# ADC_Circuit.net
KiCad netlist of a schematic drawn in Altium Designer
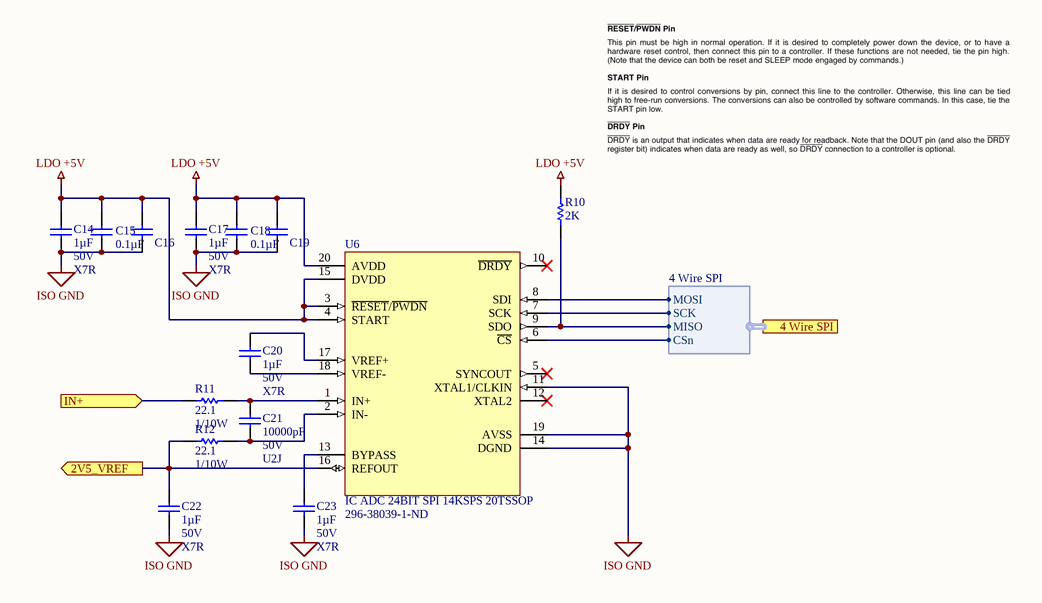
[diagram p0: ADC_Circuit.SchDoc]

(export (version "E")
  (design (tool "Eeschema 10.0.6"))
  (components
    (comp (ref "C14")
      (value "CAP CER 1UF 50V 10% X7R 0603")
      (footprint "CAP, 0603")
      (description "1µF ±10% 50V Ceramic Capacitor X7R 0603 (1608 Metric)")
      (fields
        (field (name "TOLERANCE") "±10%")
        (field (name "CAPACITANCE") "1µF")
        (field (name "VOLTAGE") "50V")
        (field (name "TEMPERATURE COEFFICIENT") "X7R")
      )
      (libsource (lib "Schematic Diagrams") (part "CAP CER 1UF 50V 10% X7R 0603"))
    )
    (comp (ref "C15")
      (value "CAP CER 0.1UF 50V 10% X7R 0603")
      (footprint "CAP, 0603")
      (description "0.10µF ±10% 50V Ceramic Capacitor X7R 0603 (1608 Metric)")
      (fields
        (field (name "TOLERANCE") "±10%")
        (field (name "CAPACITANCE") "0.1µF")
        (field (name "VOLTAGE") "50V")
      )
      (libsource (lib "Schematic Diagrams") (part "CAP CER 0.1UF 50V 10% X7R 0603"))
    )
    (comp (ref "C16")
      (value "CAP CER 0.022UF 50V 10% X7R 0603")
      (footprint "CAP, 0603")
      (description "0.022µF ±10% 50V Ceramic Capacitor X7R 0603 (1608 Metric)")
      (fields (field (name "TOLERANCE") "±10%"))
      (libsource (lib "Schematic Diagrams") (part "CAP CER 0.022UF 50V 10% X7R 0603"))
    )
    (comp (ref "C17")
      (value "CAP CER 1UF 50V 10% X7R 0603")
      (footprint "CAP, 0603")
      (description "1µF ±10% 50V Ceramic Capacitor X7R 0603 (1608 Metric)")
      (fields
        (field (name "TOLERANCE") "±10%")
        (field (name "CAPACITANCE") "1µF")
        (field (name "VOLTAGE") "50V")
        (field (name "TEMPERATURE COEFFICIENT") "X7R")
      )
      (libsource (lib "Schematic Diagrams") (part "CAP CER 1UF 50V 10% X7R 0603"))
    )
    (comp (ref "C18")
      (value "CAP CER 0.1UF 50V 10% X7R 0603")
      (footprint "CAP, 0603")
      (description "0.10µF ±10% 50V Ceramic Capacitor X7R 0603 (1608 Metric)")
      (fields
        (field (name "TOLERANCE") "±10%")
        (field (name "CAPACITANCE") "0.1µF")
        (field (name "VOLTAGE") "50V")
      )
      (libsource (lib "Schematic Diagrams") (part "CAP CER 0.1UF 50V 10% X7R 0603"))
    )
    (comp (ref "C19")
      (value "CAP CER 0.022UF 50V 10% X7R 0603")
      (footprint "CAP, 0603")
      (description "0.022µF ±10% 50V Ceramic Capacitor X7R 0603 (1608 Metric)")
      (fields (field (name "TOLERANCE") "±10%"))
      (libsource (lib "Schematic Diagrams") (part "CAP CER 0.022UF 50V 10% X7R 0603"))
    )
    (comp (ref "C20")
      (value "CAP CER 1UF 50V 10% X7R 0603")
      (footprint "CAP, 0603")
      (description "1µF ±10% 50V Ceramic Capacitor X7R 0603 (1608 Metric)")
      (fields
        (field (name "TOLERANCE") "±10%")
        (field (name "CAPACITANCE") "1µF")
        (field (name "VOLTAGE") "50V")
        (field (name "TEMPERATURE COEFFICIENT") "X7R")
      )
      (libsource (lib "Schematic Diagrams") (part "CAP CER 1UF 50V 10% X7R 0603"))
    )
    (comp (ref "C21")
      (value "CAP CER 10nF 50V 5% X7R 0603")
      (footprint "CAP, 0603")
      (description "10000pF ±5% 50V Ceramic Capacitor U2J 0603 (1608 Metric)")
      (fields
        (field (name "TOLERANCE") "±5%")
        (field (name "CAPACITANCE") "10000pF")
        (field (name "VOLTAGE") "50V")
        (field (name "TEMPERATURE COEFFICIENT") "U2J")
      )
      (libsource (lib "Schematic Diagrams") (part "CAP CER 10nF 50V 5% X7R 0603"))
    )
    (comp (ref "C22")
      (value "CAP CER 1UF 50V 10% X7R 0603")
      (footprint "CAP, 0603")
      (description "1µF ±10% 50V Ceramic Capacitor X7R 0603 (1608 Metric)")
      (fields
        (field (name "TOLERANCE") "±10%")
        (field (name "CAPACITANCE") "1µF")
        (field (name "VOLTAGE") "50V")
        (field (name "TEMPERATURE COEFFICIENT") "X7R")
      )
      (libsource (lib "Schematic Diagrams") (part "CAP CER 1UF 50V 10% X7R 0603"))
    )
    (comp (ref "C23")
      (value "CAP CER 1UF 50V 10% X7R 0603")
      (footprint "CAP, 0603")
      (description "1µF ±10% 50V Ceramic Capacitor X7R 0603 (1608 Metric)")
      (fields
        (field (name "TOLERANCE") "±10%")
        (field (name "CAPACITANCE") "1µF")
        (field (name "VOLTAGE") "50V")
        (field (name "TEMPERATURE COEFFICIENT") "X7R")
      )
      (libsource (lib "Schematic Diagrams") (part "CAP CER 1UF 50V 10% X7R 0603"))
    )
    (comp (ref "R10")
      (value "2K")
      (footprint "RES, 0603")
      (description "2k Ohm ±1% 0.1W, 1/10W Chip Resistor 0603 (1608 Metric) Moisture Resistant Thick Film")
      (fields
        (field (name "MANUFACTURER") "Yageo")
        (field (name "MANUFACTURER PART NUMBER") "RC0603FR-072KL")
      )
      (libsource (lib "Schematic Diagrams") (part "RES 2K OHM 1% 1/10W 0603"))
    )
    (comp (ref "R11")
      (value "RES 22.1 OHM 1% 1/10W 0603")
      (footprint "RES, 0603")
      (description "22.1 Ohm ±1% 0.1W, 1/10W Chip Resistor 0603 (1608 Metric) Moisture Resistant Thick Film")
      (fields
        (field (name "TOLERANCE") "±1%")
        (field (name "RESISTANCE") "22.1")
        (field (name "POWER") "1/10W")
      )
      (libsource (lib "Schematic Diagrams") (part "RES 22.1 OHM 1% 1/10W 0603"))
    )
    (comp (ref "R12")
      (value "RES 22.1 OHM 1% 1/10W 0603")
      (footprint "RES, 0603")
      (description "22.1 Ohm ±1% 0.1W, 1/10W Chip Resistor 0603 (1608 Metric) Moisture Resistant Thick Film")
      (fields
        (field (name "TOLERANCE") "±1%")
        (field (name "RESISTANCE") "22.1")
        (field (name "POWER") "1/10W")
      )
      (libsource (lib "Schematic Diagrams") (part "RES 22.1 OHM 1% 1/10W 0603"))
    )
    (comp (ref "U6")
      (value "IC ADC 24BIT SPI 14KSPS 20TSSOP")
      (footprint "TSSOP65P640X120-20N")
      (description "24 Bit Analog to Digital Converter 1 Input 1 Sigma-Delta 20-TSSOP")
      (fields
        (field (name "SUPPLIER PART NUMBER 1") "296-38039-1-ND")
        (field (name "MANUFACTURER") "Texas Instruments")
        (field (name "MANUFACTURER PART NUMBER") "ADS1259QPWRQ1")
      )
      (libsource (lib "Schematic Diagrams") (part "IC ADC 24BIT SPI 14KSPS 20TSSOP"))
    )
  )
  (nets
    (net (code "4") (name "/2V5_VREF") (class "Default")
      (node (ref "C22") (pin "1") (pinfunction "1_1") (pintype "passive"))
      (node (ref "R12") (pin "1") (pinfunction "1_1") (pintype "passive"))
      (node (ref "U6") (pin "16") (pinfunction "REFOUT_16") (pintype "bidirectional"))
    )
    (net (code "5") (name "/CSn") (class "Default")
      (node (ref "U6") (pin "6") (pinfunction "~{CS}_6") (pintype "input"))
    )
    (net (code "6") (name "/IN+") (class "Default")
      (node (ref "R11") (pin "1") (pinfunction "1_1") (pintype "passive"))
    )
    (net (code "7") (name "/MISO") (class "Default")
      (node (ref "R10") (pin "2") (pinfunction "2_2") (pintype "passive"))
      (node (ref "U6") (pin "9") (pinfunction "SDO_9") (pintype "output"))
    )
    (net (code "8") (name "/MOSI") (class "Default")
      (node (ref "U6") (pin "8") (pinfunction "SDI_8") (pintype "input"))
    )
    (net (code "9") (name "/SCK") (class "Default")
      (node (ref "U6") (pin "7") (pinfunction "SCK_7") (pintype "input"))
    )
    (net (code "11") (name "ISO GND") (class "Default")
      (node (ref "C14") (pin "2") (pinfunction "2_2") (pintype "passive"))
      (node (ref "C15") (pin "2") (pinfunction "2_2") (pintype "passive"))
      (node (ref "C16") (pin "2") (pinfunction "2_2") (pintype "passive"))
      (node (ref "C17") (pin "2") (pinfunction "2_2") (pintype "passive"))
      (node (ref "C18") (pin "2") (pinfunction "2_2") (pintype "passive"))
      (node (ref "C19") (pin "2") (pinfunction "2_2") (pintype "passive"))
      (node (ref "C22") (pin "2") (pinfunction "2_2") (pintype "passive"))
      (node (ref "C23") (pin "2") (pinfunction "2_2") (pintype "passive"))
      (node (ref "U6") (pin "11") (pinfunction "XTAL1/CLKIN_11") (pintype "input"))
      (node (ref "U6") (pin "14") (pinfunction "DGND_14") (pintype "passive"))
      (node (ref "U6") (pin "19") (pinfunction "AVSS_19") (pintype "passive"))
    )
    (net (code "12") (name "LDO +5V") (class "Default")
      (node (ref "C14") (pin "1") (pinfunction "1_1") (pintype "passive"))
      (node (ref "C15") (pin "1") (pinfunction "1_1") (pintype "passive"))
      (node (ref "C16") (pin "1") (pinfunction "1_1") (pintype "passive"))
      (node (ref "C17") (pin "1") (pinfunction "1_1") (pintype "passive"))
      (node (ref "C18") (pin "1") (pinfunction "1_1") (pintype "passive"))
      (node (ref "C19") (pin "1") (pinfunction "1_1") (pintype "passive"))
      (node (ref "R10") (pin "1") (pinfunction "1_1") (pintype "passive"))
      (node (ref "U6") (pin "15") (pinfunction "DVDD_15") (pintype "passive"))
      (node (ref "U6") (pin "20") (pinfunction "AVDD_20") (pintype "passive"))
      (node (ref "U6") (pin "3") (pinfunction "~{RESET}/~{PWDN}_3") (pintype "input"))
      (node (ref "U6") (pin "4") (pinfunction "START_4") (pintype "input"))
    )
    (net (code "13") (name "Net-(U6-BYPASS)") (class "Default")
      (node (ref "C23") (pin "1") (pinfunction "1_1") (pintype "passive"))
      (node (ref "U6") (pin "13") (pinfunction "BYPASS_13") (pintype "passive"))
    )
    (net (code "14") (name "Net-(U6-IN+)") (class "Default")
      (node (ref "C21") (pin "1") (pinfunction "1_1") (pintype "passive"))
      (node (ref "R11") (pin "2") (pinfunction "2_2") (pintype "passive"))
      (node (ref "U6") (pin "1") (pinfunction "IN+_1") (pintype "input"))
    )
    (net (code "15") (name "Net-(U6-IN-)") (class "Default")
      (node (ref "C21") (pin "2") (pinfunction "2_2") (pintype "passive"))
      (node (ref "R12") (pin "2") (pinfunction "2_2") (pintype "passive"))
      (node (ref "U6") (pin "2") (pinfunction "IN-_2") (pintype "input"))
    )
    (net (code "16") (name "Net-(U6-VREF+)") (class "Default")
      (node (ref "C20") (pin "1") (pinfunction "1_1") (pintype "passive"))
      (node (ref "U6") (pin "17") (pinfunction "VREF+_17") (pintype "input"))
    )
    (net (code "17") (name "Net-(U6-VREF-)") (class "Default")
      (node (ref "C20") (pin "2") (pinfunction "2_2") (pintype "passive"))
      (node (ref "U6") (pin "18") (pinfunction "VREF-_18") (pintype "input"))
    )
    (net (code "18") (name "unconnected-(U6-SYNCOUT-Pad5)") (class "Default")
      (node (ref "U6") (pin "5") (pinfunction "SYNCOUT_5") (pintype "output+no_connect"))
    )
    (net (code "19") (name "unconnected-(U6-XTAL2-Pad12)") (class "Default")
      (node (ref "U6") (pin "12") (pinfunction "XTAL2_12") (pintype "passive+no_connect"))
    )
    (net (code "20") (name "unconnected-(U6-~{DRDY}-Pad10)") (class "Default")
      (node (ref "U6") (pin "10") (pinfunction "~{DRDY}_10") (pintype "output+no_connect"))
    )
  )
)
